# 1-Schematic_Nanomixel.net
KiCad netlist of a schematic drawn in EasyEDA
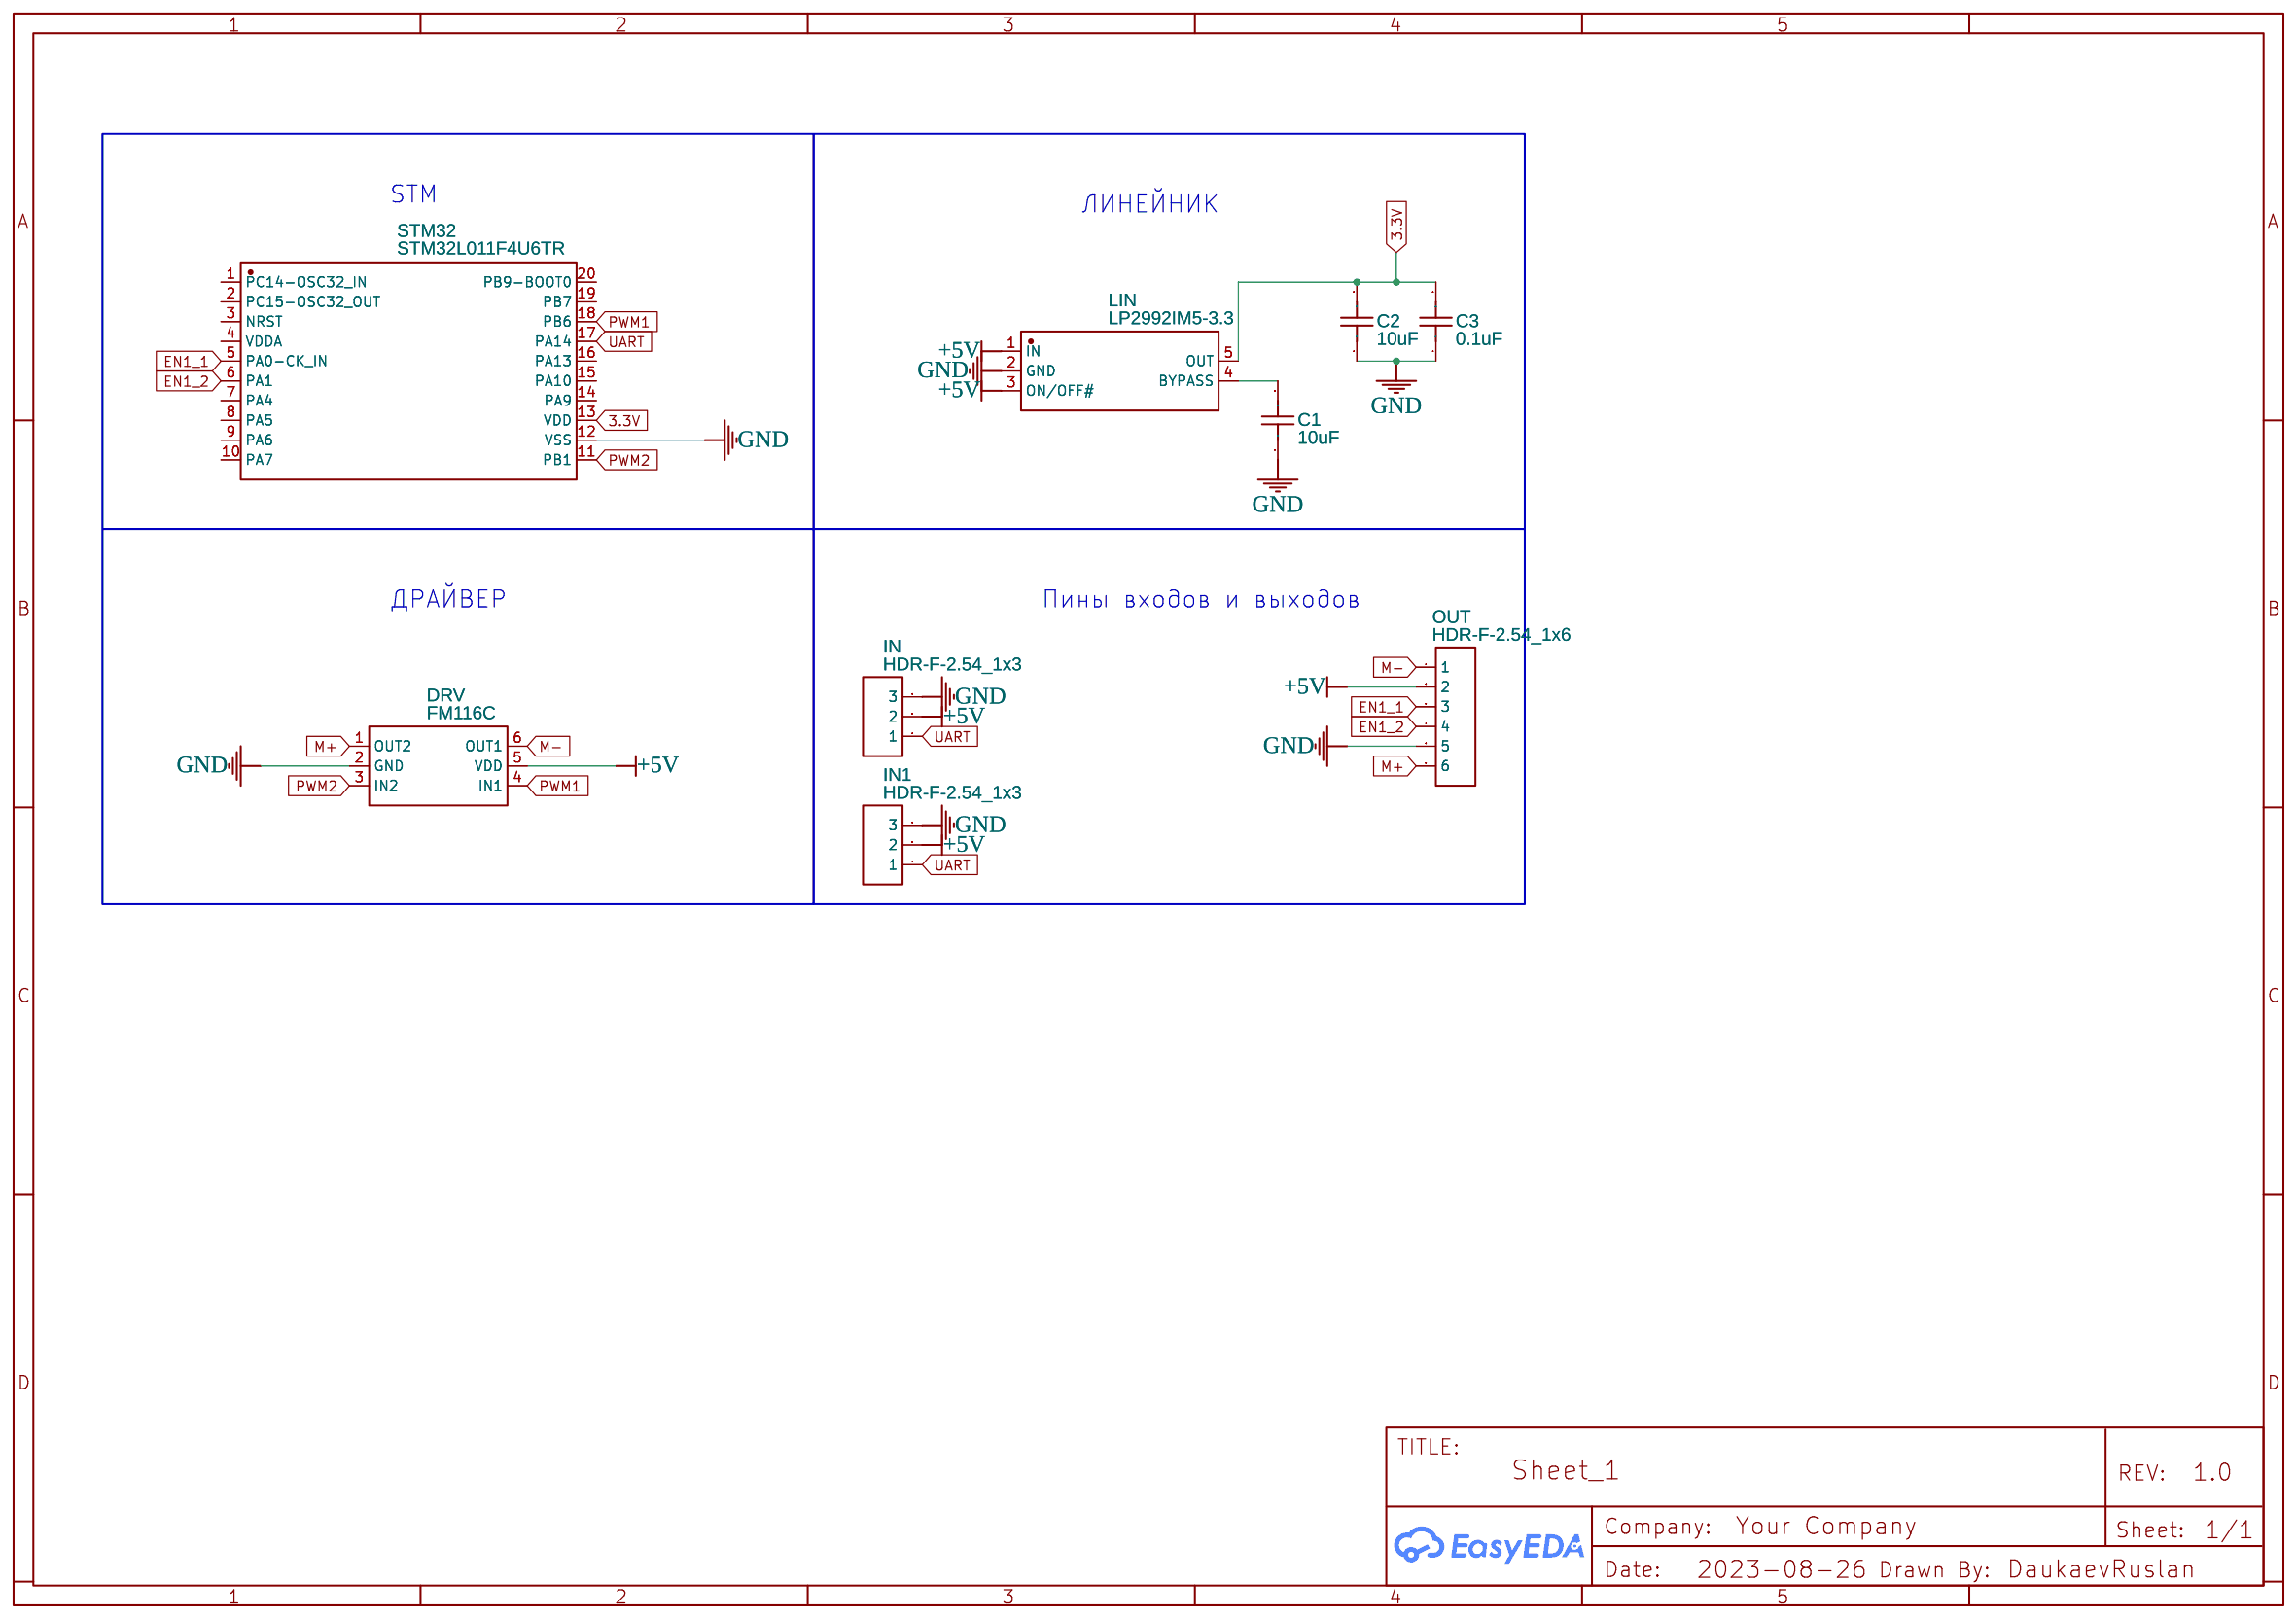
[diagram p0: schematic sheet]

(export (version "E")
  (design (tool "Eeschema 10.0.6"))
  (components
    (comp (ref "C1") (value "10uF") (libsource (lib "") (part "C_0603_US")))
    (comp (ref "C2") (value "10uF") (libsource (lib "") (part "C_0603_US")))
    (comp (ref "C3") (value "0.1uF") (libsource (lib "") (part "C_0603_US")))
    (comp (ref "DRV")
      (value "FM116C")
      (fields (field (name "Manufacturer") "FM富满"))
      (libsource (lib "") (part "FM116C"))
    )
    (comp (ref "IN") (value "HDR-F-2.54_1x3") (libsource (lib "") (part "HDR-F-2.54_1x3")))
    (comp (ref "IN1") (value "HDR-F-2.54_1x3") (libsource (lib "") (part "HDR-F-2.54_1x3")))
    (comp (ref "LIN")
      (value "LP2992IM5-3.3")
      (fields (field (name "Manufacturer") "TI(德州仪器)"))
      (libsource (lib "") (part "LP2992IM5-3.3"))
    )
    (comp (ref "OUT") (value "HDR-F-2.54_1x6") (libsource (lib "") (part "HDR-F-2.54_1x6")))
    (comp (ref "STM32")
      (value "STM32L011F4U6TR")
      (fields (field (name "Manufacturer") "ST(意法半导体)"))
      (libsource (lib "") (part "STM32L011F4U6TR"))
    )
  )
  (nets
    (net (code "1") (name "+5V") (class "Default")
      (node (ref "DRV") (pin "5") (pinfunction "VDD_5") (pintype "unspecified"))
      (node (ref "IN") (pin "2") (pinfunction "2_2") (pintype "input"))
      (node (ref "IN1") (pin "2") (pinfunction "2_2") (pintype "input"))
      (node (ref "LIN") (pin "1") (pinfunction "IN_1") (pintype "unspecified"))
      (node (ref "LIN") (pin "3") (pinfunction "ON/OFF#_3") (pintype "unspecified"))
      (node (ref "OUT") (pin "2") (pinfunction "2_2") (pintype "input"))
    )
    (net (code "2") (name "3.3V") (class "Default")
      (node (ref "C2") (pin "2") (pinfunction "2_2") (pintype "unspecified"))
      (node (ref "C3") (pin "2") (pinfunction "2_2") (pintype "unspecified"))
      (node (ref "LIN") (pin "5") (pinfunction "OUT_5") (pintype "unspecified"))
      (node (ref "STM32") (pin "13") (pinfunction "VDD_13") (pintype "unspecified"))
    )
    (net (code "3") (name "EN1_1") (class "Default")
      (node (ref "OUT") (pin "3") (pinfunction "3_3") (pintype "input"))
      (node (ref "STM32") (pin "5") (pinfunction "PA0-CK_IN_5") (pintype "unspecified"))
    )
    (net (code "4") (name "EN1_2") (class "Default")
      (node (ref "OUT") (pin "4") (pinfunction "4_4") (pintype "input"))
      (node (ref "STM32") (pin "6") (pinfunction "PA1_6") (pintype "unspecified"))
    )
    (net (code "5") (name "GND") (class "Default")
      (node (ref "C1") (pin "1") (pinfunction "1_1") (pintype "unspecified"))
      (node (ref "C2") (pin "1") (pinfunction "1_1") (pintype "unspecified"))
      (node (ref "C3") (pin "1") (pinfunction "1_1") (pintype "unspecified"))
      (node (ref "DRV") (pin "2") (pinfunction "GND_2") (pintype "unspecified"))
      (node (ref "IN") (pin "3") (pinfunction "3_3") (pintype "input"))
      (node (ref "IN1") (pin "3") (pinfunction "3_3") (pintype "input"))
      (node (ref "LIN") (pin "2") (pinfunction "GND_2") (pintype "unspecified"))
      (node (ref "OUT") (pin "5") (pinfunction "5_5") (pintype "input"))
      (node (ref "STM32") (pin "12") (pinfunction "VSS_12") (pintype "unspecified"))
    )
    (net (code "6") (name "M+") (class "Default")
      (node (ref "DRV") (pin "1") (pinfunction "OUT2_1") (pintype "unspecified"))
      (node (ref "OUT") (pin "6") (pinfunction "6_6") (pintype "input"))
    )
    (net (code "7") (name "M-") (class "Default")
      (node (ref "DRV") (pin "6") (pinfunction "OUT1_6") (pintype "unspecified"))
      (node (ref "OUT") (pin "1") (pinfunction "1_1") (pintype "input"))
    )
    (net (code "8") (name "Net-(LIN-BYPASS)") (class "Default")
      (node (ref "C1") (pin "2") (pinfunction "2_2") (pintype "unspecified"))
      (node (ref "LIN") (pin "4") (pinfunction "BYPASS_4") (pintype "unspecified"))
    )
    (net (code "9") (name "PWM1") (class "Default")
      (node (ref "DRV") (pin "4") (pinfunction "IN1_4") (pintype "unspecified"))
      (node (ref "STM32") (pin "18") (pinfunction "PB6_18") (pintype "unspecified"))
    )
    (net (code "10") (name "PWM2") (class "Default")
      (node (ref "DRV") (pin "3") (pinfunction "IN2_3") (pintype "unspecified"))
      (node (ref "STM32") (pin "11") (pinfunction "PB1_11") (pintype "unspecified"))
    )
    (net (code "11") (name "UART") (class "Default")
      (node (ref "IN") (pin "1") (pinfunction "1_1") (pintype "input"))
      (node (ref "IN1") (pin "1") (pinfunction "1_1") (pintype "input"))
      (node (ref "STM32") (pin "17") (pinfunction "PA14_17") (pintype "unspecified"))
    )
    (net (code "12") (name "unconnected-(STM32-NRST-Pad3)") (class "Default")
      (node (ref "STM32") (pin "3") (pinfunction "NRST_3") (pintype "unspecified"))
    )
    (net (code "13") (name "unconnected-(STM32-PA4-Pad7)") (class "Default")
      (node (ref "STM32") (pin "7") (pinfunction "PA4_7") (pintype "unspecified"))
    )
    (net (code "14") (name "unconnected-(STM32-PA5-Pad8)") (class "Default")
      (node (ref "STM32") (pin "8") (pinfunction "PA5_8") (pintype "unspecified"))
    )
    (net (code "15") (name "unconnected-(STM32-PA6-Pad9)") (class "Default")
      (node (ref "STM32") (pin "9") (pinfunction "PA6_9") (pintype "unspecified"))
    )
    (net (code "16") (name "unconnected-(STM32-PA7-Pad10)") (class "Default")
      (node (ref "STM32") (pin "10") (pinfunction "PA7_10") (pintype "unspecified"))
    )
    (net (code "17") (name "unconnected-(STM32-PA9-Pad14)") (class "Default")
      (node (ref "STM32") (pin "14") (pinfunction "PA9_14") (pintype "unspecified"))
    )
    (net (code "18") (name "unconnected-(STM32-PA10-Pad15)") (class "Default")
      (node (ref "STM32") (pin "15") (pinfunction "PA10_15") (pintype "unspecified"))
    )
    (net (code "19") (name "unconnected-(STM32-PA13-Pad16)") (class "Default")
      (node (ref "STM32") (pin "16") (pinfunction "PA13_16") (pintype "unspecified"))
    )
    (net (code "20") (name "unconnected-(STM32-PB7-Pad19)") (class "Default")
      (node (ref "STM32") (pin "19") (pinfunction "PB7_19") (pintype "unspecified"))
    )
    (net (code "21") (name "unconnected-(STM32-PB9-BOOT0-Pad20)") (class "Default")
      (node (ref "STM32") (pin "20") (pinfunction "PB9-BOOT0_20") (pintype "unspecified"))
    )
    (net (code "22") (name "unconnected-(STM32-PC14-OSC32_IN-Pad1)") (class "Default")
      (node (ref "STM32") (pin "1") (pinfunction "PC14-OSC32_IN_1") (pintype "unspecified"))
    )
    (net (code "23") (name "unconnected-(STM32-PC15-OSC32_OUT-Pad2)") (class "Default")
      (node (ref "STM32") (pin "2") (pinfunction "PC15-OSC32_OUT_2") (pintype "unspecified"))
    )
    (net (code "24") (name "unconnected-(STM32-VDDA-Pad4)") (class "Default")
      (node (ref "STM32") (pin "4") (pinfunction "VDDA_4") (pintype "unspecified"))
    )
  )
)
